# SP501e.net
KiCad netlist of a schematic drawn in EasyEDA
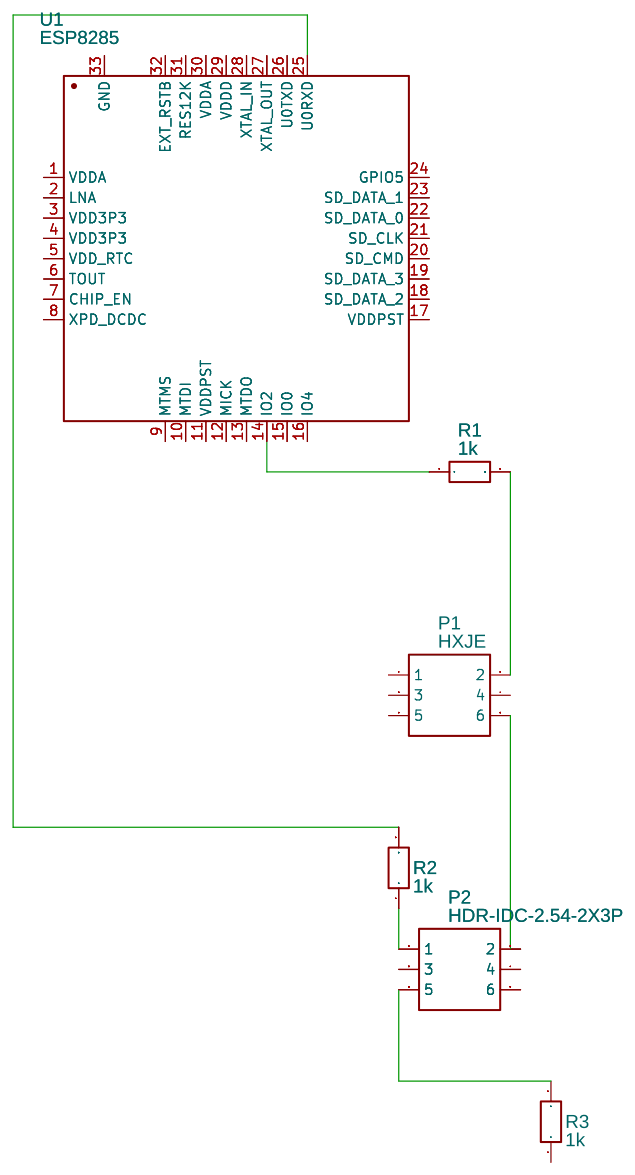
[diagram p0: Sheet_1]
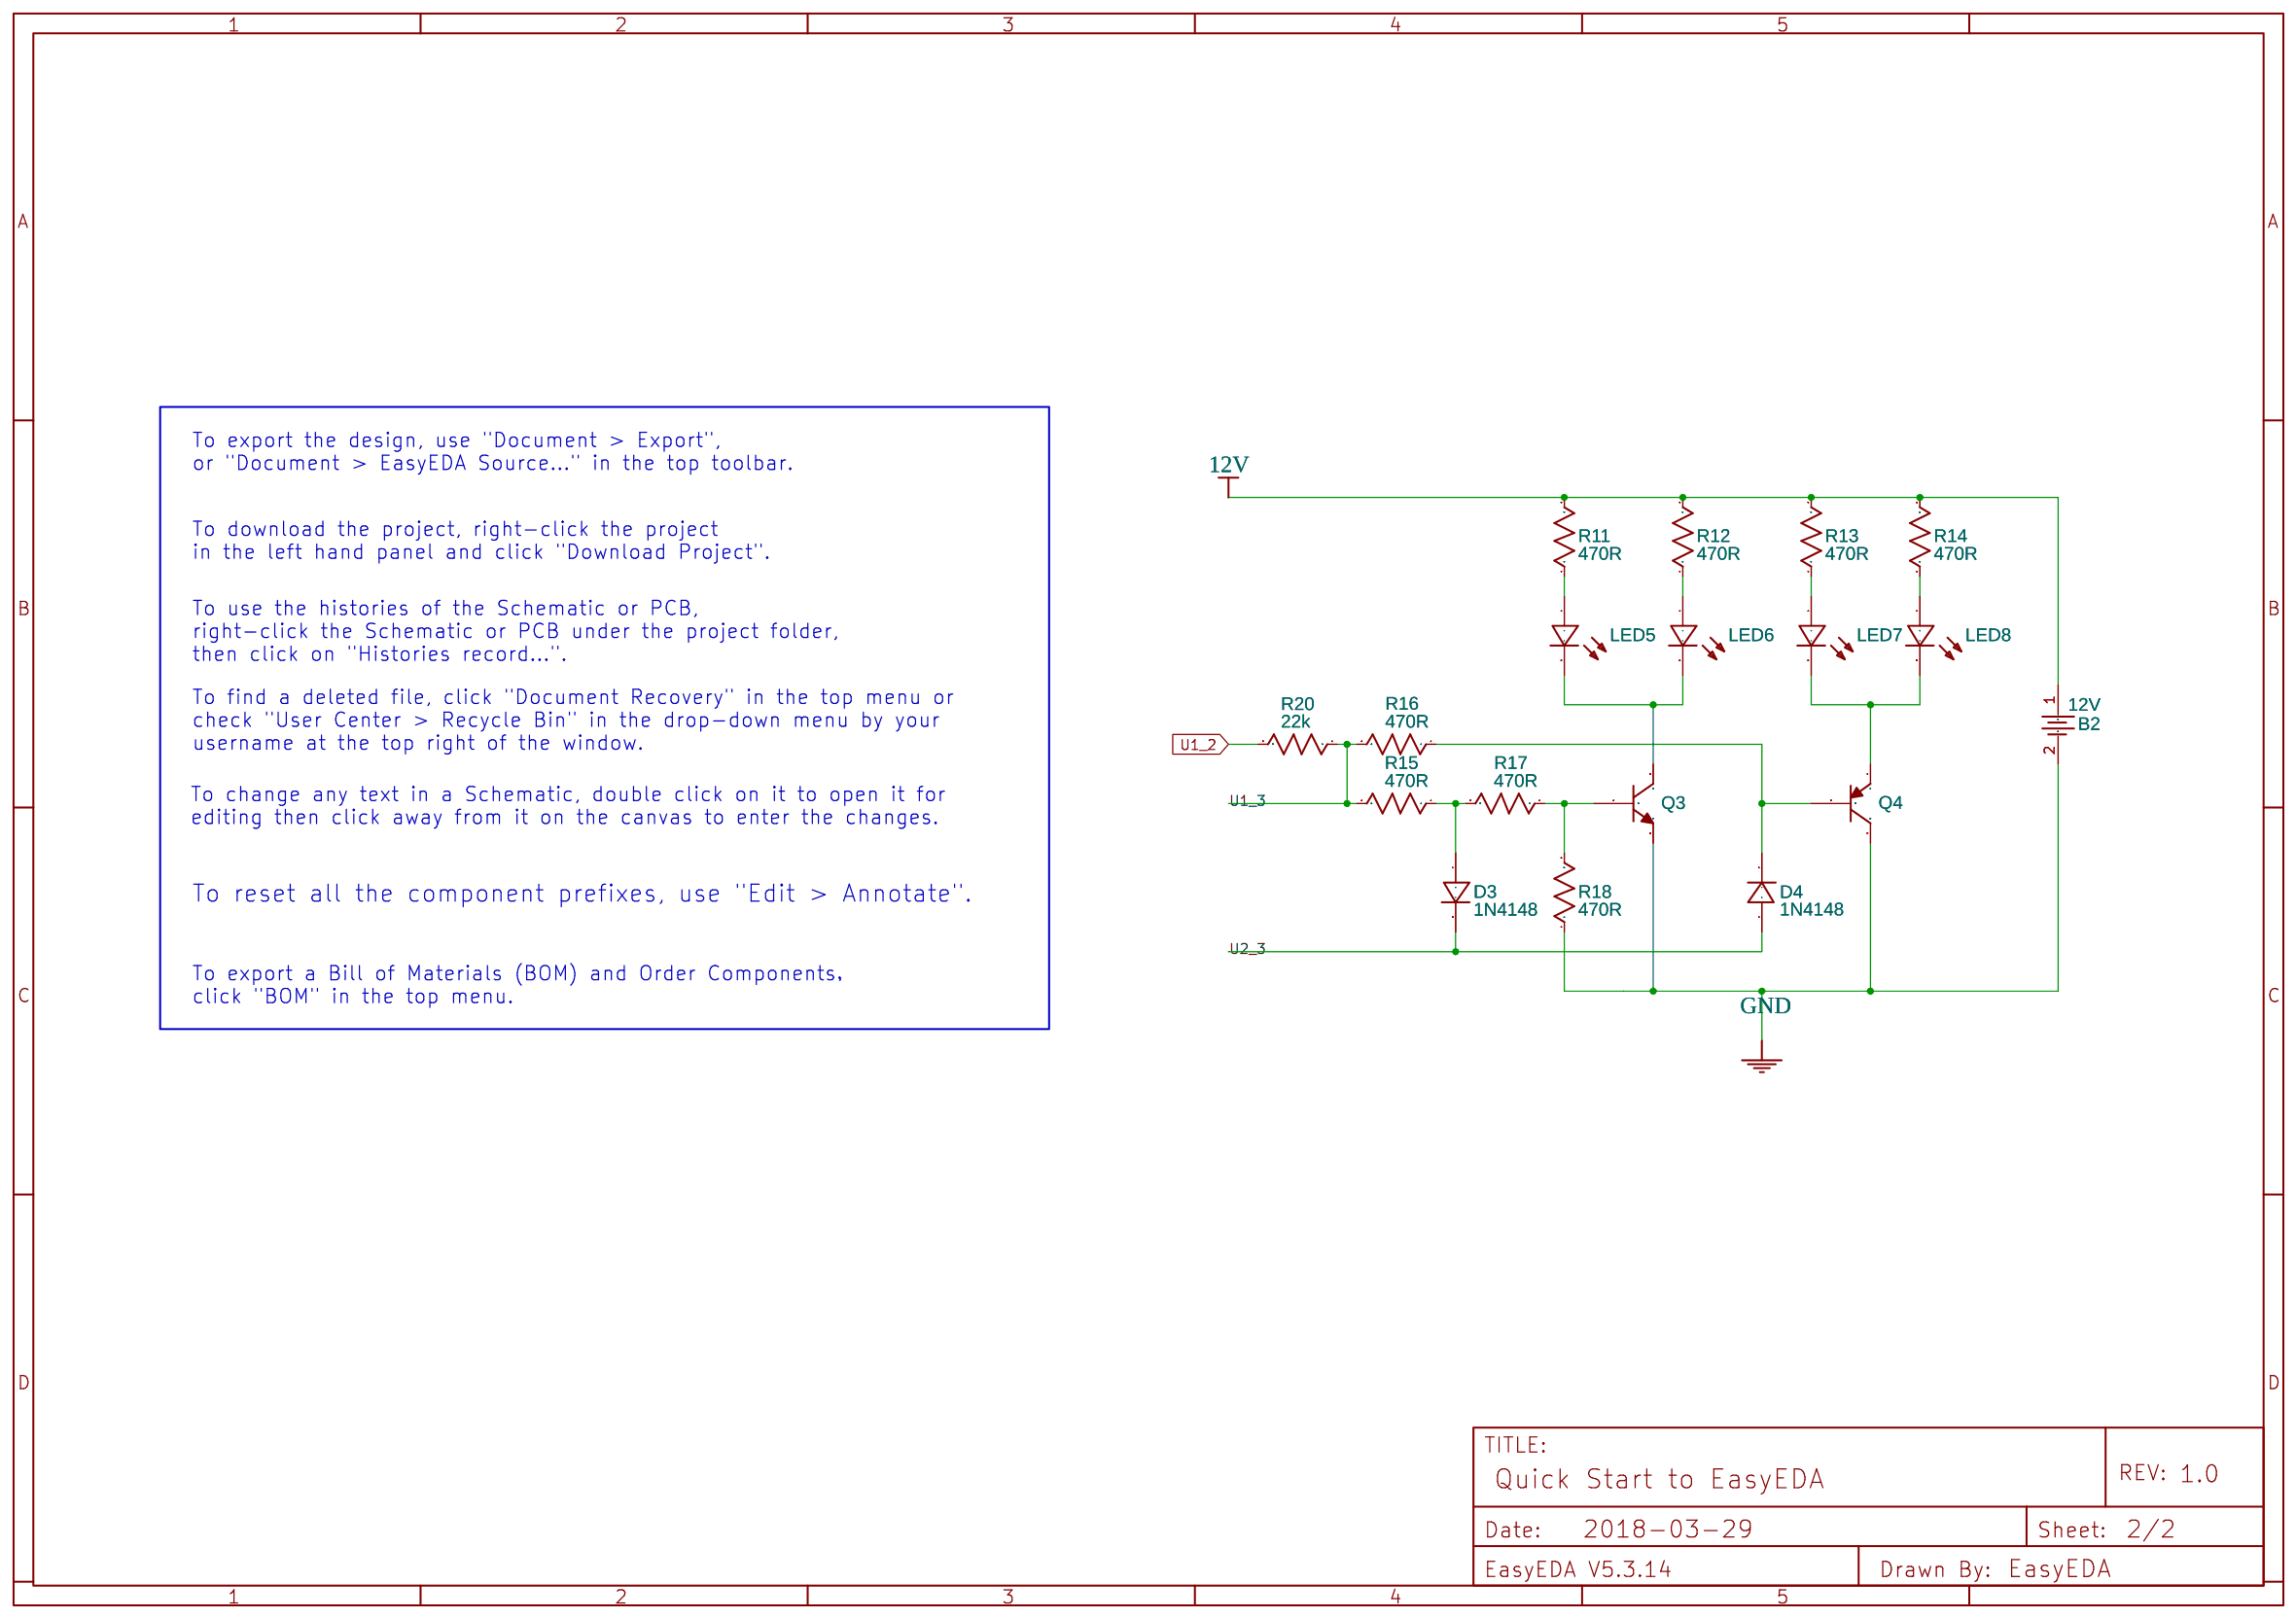
[diagram p1: Sheet_2]

(export (version "E")
  (design (tool "Eeschema 10.0.6"))
  (components
    (comp (ref "P1")
      (value "HXJE")
      (fields
        (field (name "BOM_Manufacturer Part") "2X3 2.54mm IDC Box")
        (field (name "BOM_Supplier Part") "C11214")
      )
      (libsource (lib "") (part "HDR-IDC-2.54-2X3P"))
    )
    (comp (ref "P2")
      (value "HDR-IDC-2.54-2X3P")
      (fields
        (field (name "BOM_Manufacturer Part") "2X3 2.54mm IDC Box")
        (field (name "BOM_Supplier Part") "C11214")
      )
      (libsource (lib "") (part "HDR-IDC-2.54-2X3P"))
    )
    (comp (ref "R1") (value "1k") (libsource (lib "") (part "Res_AXIAL-0.3(1/8W)_EU_1")))
    (comp (ref "R2") (value "1k") (libsource (lib "") (part "Res_AXIAL-0.3(1/8W)_EU")))
    (comp (ref "R3") (value "1k") (libsource (lib "") (part "Res_AXIAL-0.3(1/8W)_EU")))
    (comp (ref "U1")
      (value "ESP8285")
      (fields (field (name "BOM_Supplier Part") "C83901"))
      (libsource (lib "") (part "ESP8285"))
    )
    (comp (ref "B2")
      (value "12V")
      (fields (field (name "BOM_Manufacturer Part") "BS-2-1") (field (name "BOM_Supplier Part") "C70376"))
      (libsource (lib "") (part "Unknown_1035_360"))
    )
    (comp (ref "D3")
      (value "1N4148")
      (fields (field (name "BOM_Manufacturer Part") "?"))
      (libsource (lib "") (part "Unknown_730_445"))
    )
    (comp (ref "D4")
      (value "1N4148")
      (fields (field (name "BOM_Manufacturer Part") "?"))
      (libsource (lib "") (part "Unknown_885_445"))
    )
    (comp (ref "LED5")
      (value "LED-Blue(0603)")
      (fields (field (name "BOM_Manufacturer Part") "19-217/BHC-ZL1M2RY/3T"))
      (libsource (lib "") (part "Unknown_785_315"))
    )
    (comp (ref "LED6")
      (value "LED-Blue(0603)")
      (fields (field (name "BOM_Manufacturer Part") "19-217/BHC-ZL1M2RY/3T"))
      (libsource (lib "") (part "Unknown_845_315"))
    )
    (comp (ref "LED7")
      (value "LED-Blue(0603)")
      (fields (field (name "BOM_Manufacturer Part") "19-217/BHC-ZL1M2RY/3T"))
      (libsource (lib "") (part "Unknown_910_315"))
    )
    (comp (ref "LED8")
      (value "LED-Blue(0603)")
      (fields (field (name "BOM_Manufacturer Part") "19-217/BHC-ZL1M2RY/3T"))
      (libsource (lib "") (part "Unknown_965_315"))
    )
    (comp (ref "Q3") (value "BC547B Tube") (libsource (lib "") (part "Unknown_820_400")))
    (comp (ref "Q4") (value "2N3906") (libsource (lib "") (part "Unknown_930_400")))
    (comp (ref "R11")
      (value "470R")
      (fields (field (name "BOM_Manufacturer Part") "?"))
      (libsource (lib "") (part "Res_AXIAL-0.3(1/8W)_US"))
    )
    (comp (ref "R12")
      (value "470R")
      (fields (field (name "BOM_Manufacturer Part") "?"))
      (libsource (lib "") (part "Res_AXIAL-0.3(1/8W)_US"))
    )
    (comp (ref "R13")
      (value "470R")
      (fields (field (name "BOM_Manufacturer Part") "?"))
      (libsource (lib "") (part "Res_AXIAL-0.3(1/8W)_US"))
    )
    (comp (ref "R14")
      (value "470R")
      (fields (field (name "BOM_Manufacturer Part") "?"))
      (libsource (lib "") (part "Res_AXIAL-0.3(1/8W)_US"))
    )
    (comp (ref "R15")
      (value "470R")
      (fields (field (name "BOM_Manufacturer Part") "?"))
      (libsource (lib "") (part "Res_AXIAL-0.3(1/8W)_US_1"))
    )
    (comp (ref "R16")
      (value "470R")
      (fields (field (name "BOM_Manufacturer Part") "?"))
      (libsource (lib "") (part "Res_AXIAL-0.3(1/8W)_US_1"))
    )
    (comp (ref "R17")
      (value "470R")
      (fields (field (name "BOM_Manufacturer Part") "?"))
      (libsource (lib "") (part "Res_AXIAL-0.3(1/8W)_US_1"))
    )
    (comp (ref "R18")
      (value "470R")
      (fields (field (name "BOM_Manufacturer Part") "?"))
      (libsource (lib "") (part "Res_AXIAL-0.3(1/8W)_US"))
    )
    (comp (ref "R20")
      (value "22k")
      (fields (field (name "BOM_Manufacturer Part") "?"))
      (libsource (lib "") (part "Res_AXIAL-0.3(1/8W)_US_1"))
    )
  )
  (nets
    (net (code "1") (name "12V") (class "Default")
      (node (ref "B2") (pin "1") (pinfunction "1_1") (pintype "input"))
      (node (ref "R11") (pin "2") (pinfunction "2_2") (pintype "unspecified"))
      (node (ref "R12") (pin "2") (pinfunction "2_2") (pintype "unspecified"))
      (node (ref "R13") (pin "2") (pinfunction "2_2") (pintype "unspecified"))
      (node (ref "R14") (pin "2") (pinfunction "2_2") (pintype "unspecified"))
    )
    (net (code "2") (name "GND") (class "Default")
      (node (ref "B2") (pin "2") (pinfunction "2_2") (pintype "input"))
      (node (ref "Q3") (pin "3") (pinfunction "E_3") (pintype "unspecified"))
      (node (ref "Q4") (pin "3") (pinfunction "C_3") (pintype "unspecified"))
      (node (ref "R18") (pin "1") (pinfunction "1_1") (pintype "unspecified"))
    )
    (net (code "3") (name "Net-(D3-+)") (class "Default")
      (node (ref "D3") (pin "1") (pinfunction "+_1") (pintype "unspecified"))
      (node (ref "R15") (pin "1") (pinfunction "1_1") (pintype "unspecified"))
      (node (ref "R17") (pin "2") (pinfunction "2_2") (pintype "unspecified"))
    )
    (net (code "4") (name "Net-(D4--)") (class "Default")
      (node (ref "D4") (pin "2") (pinfunction "-_2") (pintype "unspecified"))
      (node (ref "Q4") (pin "2") (pinfunction "B_2") (pintype "unspecified"))
      (node (ref "R16") (pin "1") (pinfunction "1_1") (pintype "unspecified"))
    )
    (net (code "5") (name "Net-(LED5-+)") (class "Default")
      (node (ref "LED5") (pin "1") (pinfunction "+_1") (pintype "unspecified"))
      (node (ref "R11") (pin "1") (pinfunction "1_1") (pintype "unspecified"))
    )
    (net (code "6") (name "Net-(LED5--)") (class "Default")
      (node (ref "LED5") (pin "2") (pinfunction "-_2") (pintype "unspecified"))
      (node (ref "LED6") (pin "2") (pinfunction "-_2") (pintype "unspecified"))
      (node (ref "Q3") (pin "1") (pinfunction "C_1") (pintype "unspecified"))
    )
    (net (code "7") (name "Net-(LED6-+)") (class "Default")
      (node (ref "LED6") (pin "1") (pinfunction "+_1") (pintype "unspecified"))
      (node (ref "R12") (pin "1") (pinfunction "1_1") (pintype "unspecified"))
    )
    (net (code "8") (name "Net-(LED7-+)") (class "Default")
      (node (ref "LED7") (pin "1") (pinfunction "+_1") (pintype "unspecified"))
      (node (ref "R13") (pin "1") (pinfunction "1_1") (pintype "unspecified"))
    )
    (net (code "9") (name "Net-(LED7--)") (class "Default")
      (node (ref "LED7") (pin "2") (pinfunction "-_2") (pintype "unspecified"))
      (node (ref "LED8") (pin "2") (pinfunction "-_2") (pintype "unspecified"))
      (node (ref "Q4") (pin "1") (pinfunction "E_1") (pintype "unspecified"))
    )
    (net (code "10") (name "Net-(LED8-+)") (class "Default")
      (node (ref "LED8") (pin "1") (pinfunction "+_1") (pintype "unspecified"))
      (node (ref "R14") (pin "1") (pinfunction "1_1") (pintype "unspecified"))
    )
    (net (code "11") (name "Net-(P1-Pad2)") (class "Default")
      (node (ref "P1") (pin "2") (pinfunction "2_2") (pintype "unspecified"))
      (node (ref "R1") (pin "2") (pinfunction "2_2") (pintype "unspecified"))
    )
    (net (code "12") (name "Net-(P1-Pad6)") (class "Default")
      (node (ref "P1") (pin "6") (pinfunction "6_6") (pintype "unspecified"))
      (node (ref "P2") (pin "2") (pinfunction "2_2") (pintype "unspecified"))
    )
    (net (code "13") (name "Net-(P2-Pad1)") (class "Default")
      (node (ref "P2") (pin "1") (pinfunction "1_1") (pintype "unspecified"))
      (node (ref "R2") (pin "1") (pinfunction "1_1") (pintype "unspecified"))
    )
    (net (code "14") (name "Net-(P2-Pad5)") (class "Default")
      (node (ref "P2") (pin "5") (pinfunction "5_5") (pintype "unspecified"))
      (node (ref "R3") (pin "2") (pinfunction "2_2") (pintype "unspecified"))
    )
    (net (code "15") (name "Net-(Q3-B)") (class "Default")
      (node (ref "Q3") (pin "2") (pinfunction "B_2") (pintype "unspecified"))
      (node (ref "R17") (pin "1") (pinfunction "1_1") (pintype "unspecified"))
      (node (ref "R18") (pin "2") (pinfunction "2_2") (pintype "unspecified"))
    )
    (net (code "16") (name "Net-(U1-IO2)") (class "Default")
      (node (ref "R1") (pin "1") (pinfunction "1_1") (pintype "unspecified"))
      (node (ref "U1") (pin "14") (pinfunction "IO2_14") (pintype "unspecified"))
    )
    (net (code "17") (name "Net-(U1-U0RXD)") (class "Default")
      (node (ref "R2") (pin "2") (pinfunction "2_2") (pintype "unspecified"))
      (node (ref "U1") (pin "25") (pinfunction "U0RXD_25") (pintype "unspecified"))
    )
    (net (code "18") (name "U1_2") (class "Default")
      (node (ref "R20") (pin "2") (pinfunction "2_2") (pintype "unspecified"))
    )
    (net (code "19") (name "U1_3") (class "Default")
      (node (ref "R15") (pin "2") (pinfunction "2_2") (pintype "unspecified"))
      (node (ref "R16") (pin "2") (pinfunction "2_2") (pintype "unspecified"))
      (node (ref "R20") (pin "1") (pinfunction "1_1") (pintype "unspecified"))
    )
    (net (code "20") (name "U2_3") (class "Default")
      (node (ref "D3") (pin "2") (pinfunction "-_2") (pintype "unspecified"))
      (node (ref "D4") (pin "1") (pinfunction "+_1") (pintype "unspecified"))
    )
    (net (code "21") (name "unconnected-(P1-Pad1)") (class "Default")
      (node (ref "P1") (pin "1") (pinfunction "1_1") (pintype "unspecified"))
    )
    (net (code "22") (name "unconnected-(P1-Pad3)") (class "Default")
      (node (ref "P1") (pin "3") (pinfunction "3_3") (pintype "unspecified"))
    )
    (net (code "23") (name "unconnected-(P1-Pad4)") (class "Default")
      (node (ref "P1") (pin "4") (pinfunction "4_4") (pintype "unspecified"))
    )
    (net (code "24") (name "unconnected-(P1-Pad5)") (class "Default")
      (node (ref "P1") (pin "5") (pinfunction "5_5") (pintype "unspecified"))
    )
    (net (code "25") (name "unconnected-(P2-Pad3)") (class "Default")
      (node (ref "P2") (pin "3") (pinfunction "3_3") (pintype "unspecified"))
    )
    (net (code "26") (name "unconnected-(P2-Pad4)") (class "Default")
      (node (ref "P2") (pin "4") (pinfunction "4_4") (pintype "unspecified"))
    )
    (net (code "27") (name "unconnected-(P2-Pad6)") (class "Default")
      (node (ref "P2") (pin "6") (pinfunction "6_6") (pintype "unspecified"))
    )
    (net (code "28") (name "unconnected-(R3-Pad1)") (class "Default")
      (node (ref "R3") (pin "1") (pinfunction "1_1") (pintype "unspecified"))
    )
    (net (code "29") (name "unconnected-(U1-CHIP_EN-Pad7)") (class "Default")
      (node (ref "U1") (pin "7") (pinfunction "CHIP_EN_7") (pintype "unspecified"))
    )
    (net (code "30") (name "unconnected-(U1-EXT_RSTB-Pad32)") (class "Default")
      (node (ref "U1") (pin "32") (pinfunction "EXT_RSTB_32") (pintype "unspecified"))
    )
    (net (code "31") (name "unconnected-(U1-GND-Pad33)") (class "Default")
      (node (ref "U1") (pin "33") (pinfunction "GND_33") (pintype "unspecified"))
    )
    (net (code "32") (name "unconnected-(U1-GPIO5-Pad24)") (class "Default")
      (node (ref "U1") (pin "24") (pinfunction "GPIO5_24") (pintype "unspecified"))
    )
    (net (code "33") (name "unconnected-(U1-IO0-Pad15)") (class "Default")
      (node (ref "U1") (pin "15") (pinfunction "IO0_15") (pintype "unspecified"))
    )
    (net (code "34") (name "unconnected-(U1-IO4-Pad16)") (class "Default")
      (node (ref "U1") (pin "16") (pinfunction "IO4_16") (pintype "unspecified"))
    )
    (net (code "35") (name "unconnected-(U1-LNA-Pad2)") (class "Default")
      (node (ref "U1") (pin "2") (pinfunction "LNA_2") (pintype "unspecified"))
    )
    (net (code "36") (name "unconnected-(U1-MICK-Pad12)") (class "Default")
      (node (ref "U1") (pin "12") (pinfunction "MICK_12") (pintype "unspecified"))
    )
    (net (code "37") (name "unconnected-(U1-MTDI-Pad10)") (class "Default")
      (node (ref "U1") (pin "10") (pinfunction "MTDI_10") (pintype "unspecified"))
    )
    (net (code "38") (name "unconnected-(U1-MTDO-Pad13)") (class "Default")
      (node (ref "U1") (pin "13") (pinfunction "MTDO_13") (pintype "unspecified"))
    )
    (net (code "39") (name "unconnected-(U1-MTMS-Pad9)") (class "Default")
      (node (ref "U1") (pin "9") (pinfunction "MTMS_9") (pintype "unspecified"))
    )
    (net (code "40") (name "unconnected-(U1-RES12K-Pad31)") (class "Default")
      (node (ref "U1") (pin "31") (pinfunction "RES12K_31") (pintype "unspecified"))
    )
    (net (code "41") (name "unconnected-(U1-SD_CLK-Pad21)") (class "Default")
      (node (ref "U1") (pin "21") (pinfunction "SD_CLK_21") (pintype "unspecified"))
    )
    (net (code "42") (name "unconnected-(U1-SD_CMD-Pad20)") (class "Default")
      (node (ref "U1") (pin "20") (pinfunction "SD_CMD_20") (pintype "unspecified"))
    )
    (net (code "43") (name "unconnected-(U1-SD_DATA_0-Pad22)") (class "Default")
      (node (ref "U1") (pin "22") (pinfunction "SD_DATA_0_22") (pintype "unspecified"))
    )
    (net (code "44") (name "unconnected-(U1-SD_DATA_1-Pad23)") (class "Default")
      (node (ref "U1") (pin "23") (pinfunction "SD_DATA_1_23") (pintype "unspecified"))
    )
    (net (code "45") (name "unconnected-(U1-SD_DATA_2-Pad18)") (class "Default")
      (node (ref "U1") (pin "18") (pinfunction "SD_DATA_2_18") (pintype "unspecified"))
    )
    (net (code "46") (name "unconnected-(U1-SD_DATA_3-Pad19)") (class "Default")
      (node (ref "U1") (pin "19") (pinfunction "SD_DATA_3_19") (pintype "unspecified"))
    )
    (net (code "47") (name "unconnected-(U1-TOUT-Pad6)") (class "Default")
      (node (ref "U1") (pin "6") (pinfunction "TOUT_6") (pintype "unspecified"))
    )
    (net (code "48") (name "unconnected-(U1-U0TXD-Pad26)") (class "Default")
      (node (ref "U1") (pin "26") (pinfunction "U0TXD_26") (pintype "unspecified"))
    )
    (net (code "49") (name "unconnected-(U1-VDD3P3-Pad3)") (class "Default")
      (node (ref "U1") (pin "3") (pinfunction "VDD3P3_3") (pintype "unspecified"))
    )
    (net (code "50") (name "unconnected-(U1-VDD3P3-Pad4)") (class "Default")
      (node (ref "U1") (pin "4") (pinfunction "VDD3P3_4") (pintype "unspecified"))
    )
    (net (code "51") (name "unconnected-(U1-VDDA-Pad1)") (class "Default")
      (node (ref "U1") (pin "1") (pinfunction "VDDA_1") (pintype "unspecified"))
    )
    (net (code "52") (name "unconnected-(U1-VDDA-Pad30)") (class "Default")
      (node (ref "U1") (pin "30") (pinfunction "VDDA_30") (pintype "unspecified"))
    )
    (net (code "53") (name "unconnected-(U1-VDDD-Pad29)") (class "Default")
      (node (ref "U1") (pin "29") (pinfunction "VDDD_29") (pintype "unspecified"))
    )
    (net (code "54") (name "unconnected-(U1-VDDPST-Pad11)") (class "Default")
      (node (ref "U1") (pin "11") (pinfunction "VDDPST_11") (pintype "unspecified"))
    )
    (net (code "55") (name "unconnected-(U1-VDDPST-Pad17)") (class "Default")
      (node (ref "U1") (pin "17") (pinfunction "VDDPST_17") (pintype "unspecified"))
    )
    (net (code "56") (name "unconnected-(U1-VDD_RTC-Pad5)") (class "Default")
      (node (ref "U1") (pin "5") (pinfunction "VDD_RTC_5") (pintype "unspecified"))
    )
    (net (code "57") (name "unconnected-(U1-XPD_DCDC-Pad8)") (class "Default")
      (node (ref "U1") (pin "8") (pinfunction "XPD_DCDC_8") (pintype "unspecified"))
    )
    (net (code "58") (name "unconnected-(U1-XTAL_IN-Pad28)") (class "Default")
      (node (ref "U1") (pin "28") (pinfunction "XTAL_IN_28") (pintype "unspecified"))
    )
    (net (code "59") (name "unconnected-(U1-XTAL_OUT-Pad27)") (class "Default")
      (node (ref "U1") (pin "27") (pinfunction "XTAL_OUT_27") (pintype "unspecified"))
    )
  )
)
